# FPGA_Power.net
KiCad netlist of a schematic drawn in Altium Designer
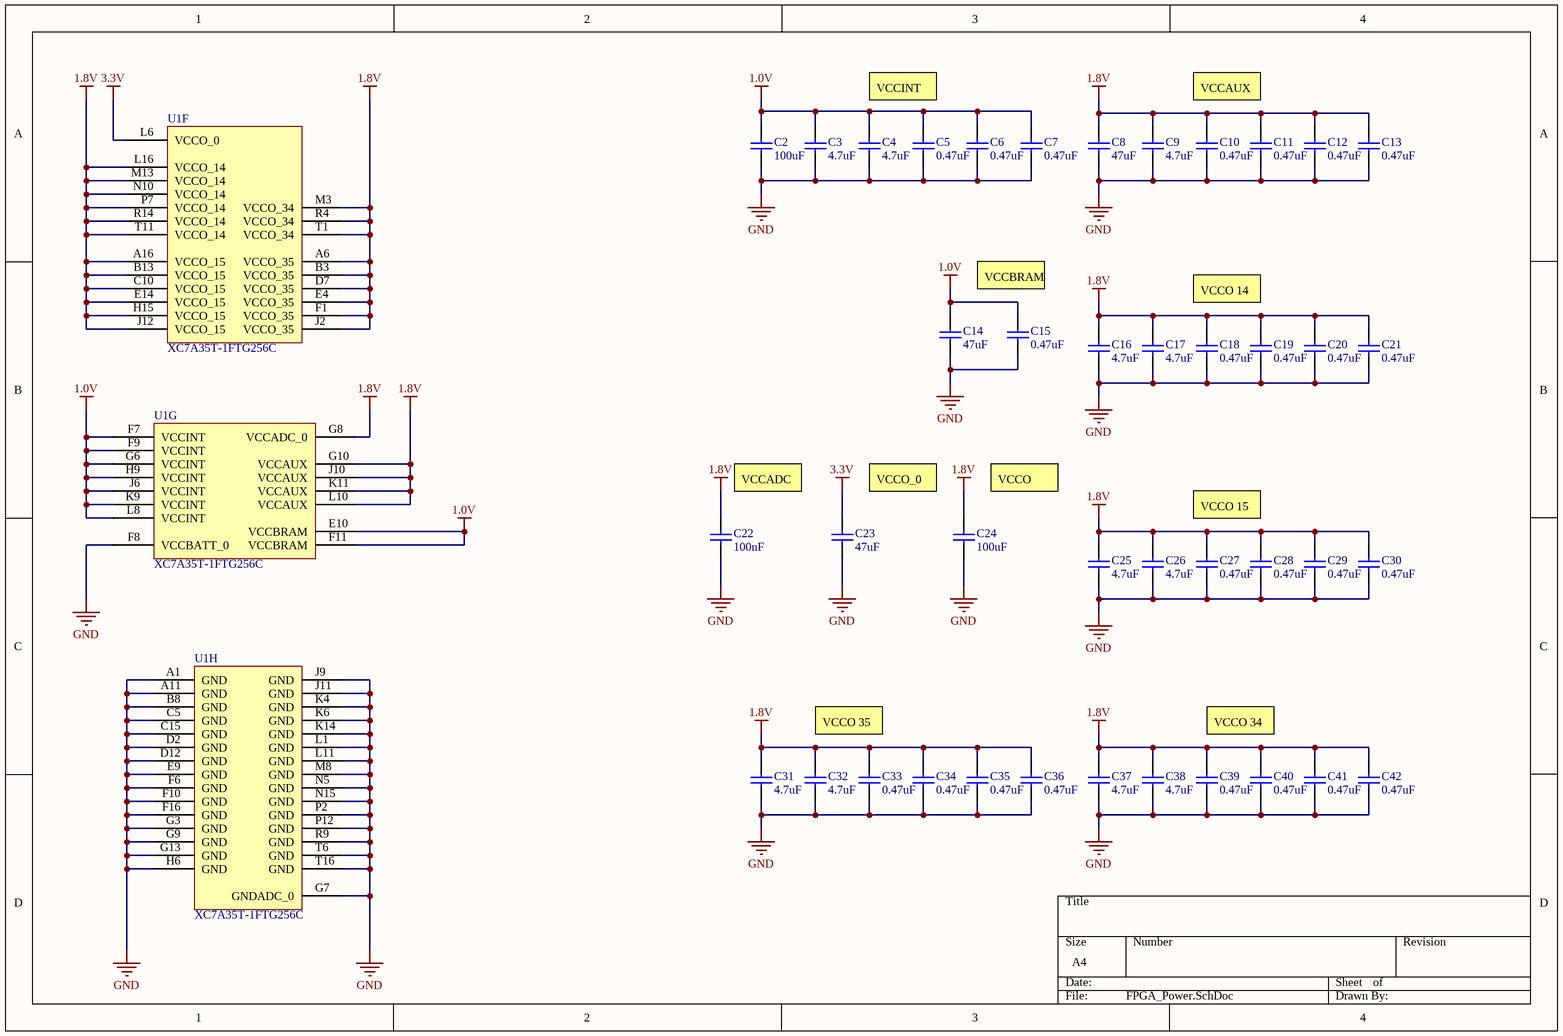
[diagram p0: FPGA_Power.SchDoc]

(export (version "E")
  (design (tool "Eeschema 10.0.6"))
  (components
    (comp (ref "C2")
      (value "100uF")
      (footprint "CAP1206")
      (fields (field (name "PART NUMBER") "GRM32ER60J107ME20L"))
      (libsource (lib "LimeMicroAltiumLib_schLib") (part "Cap_1206"))
    )
    (comp (ref "C3")
      (value "4.7uF")
      (footprint "CAP1206")
      (fields (field (name "PART NUMBER") "GRM32ER60J107ME20L"))
      (libsource (lib "LimeMicroAltiumLib_schLib") (part "Cap_1206"))
    )
    (comp (ref "C4")
      (value "4.7uF")
      (footprint "CAP1206")
      (fields (field (name "PART NUMBER") "GRM32ER60J107ME20L"))
      (libsource (lib "LimeMicroAltiumLib_schLib") (part "Cap_1206"))
    )
    (comp (ref "C5")
      (value "0.47uF")
      (footprint "CAP1206")
      (fields (field (name "PART NUMBER") "GRM32ER60J107ME20L"))
      (libsource (lib "LimeMicroAltiumLib_schLib") (part "Cap_1206"))
    )
    (comp (ref "C6")
      (value "0.47uF")
      (footprint "CAP1206")
      (fields (field (name "PART NUMBER") "GRM32ER60J107ME20L"))
      (libsource (lib "LimeMicroAltiumLib_schLib") (part "Cap_1206"))
    )
    (comp (ref "C7")
      (value "0.47uF")
      (footprint "CAP1206")
      (fields (field (name "PART NUMBER") "GRM32ER60J107ME20L"))
      (libsource (lib "LimeMicroAltiumLib_schLib") (part "Cap_1206"))
    )
    (comp (ref "C8")
      (value "47uF")
      (footprint "CAP1206")
      (fields (field (name "PART NUMBER") "GRM32ER60J107ME20L"))
      (libsource (lib "LimeMicroAltiumLib_schLib") (part "Cap_1206"))
    )
    (comp (ref "C9")
      (value "4.7uF")
      (footprint "CAP1206")
      (fields (field (name "PART NUMBER") "GRM32ER60J107ME20L"))
      (libsource (lib "LimeMicroAltiumLib_schLib") (part "Cap_1206"))
    )
    (comp (ref "C10")
      (value "0.47uF")
      (footprint "CAP1206")
      (fields (field (name "PART NUMBER") "GRM32ER60J107ME20L"))
      (libsource (lib "LimeMicroAltiumLib_schLib") (part "Cap_1206"))
    )
    (comp (ref "C11")
      (value "0.47uF")
      (footprint "CAP1206")
      (fields (field (name "PART NUMBER") "GRM32ER60J107ME20L"))
      (libsource (lib "LimeMicroAltiumLib_schLib") (part "Cap_1206"))
    )
    (comp (ref "C12")
      (value "0.47uF")
      (footprint "CAP1206")
      (fields (field (name "PART NUMBER") "GRM32ER60J107ME20L"))
      (libsource (lib "LimeMicroAltiumLib_schLib") (part "Cap_1206"))
    )
    (comp (ref "C13")
      (value "0.47uF")
      (footprint "CAP1206")
      (fields (field (name "PART NUMBER") "GRM32ER60J107ME20L"))
      (libsource (lib "LimeMicroAltiumLib_schLib") (part "Cap_1206"))
    )
    (comp (ref "C14")
      (value "47uF")
      (footprint "CAP1206")
      (fields (field (name "PART NUMBER") "GRM32ER60J107ME20L"))
      (libsource (lib "LimeMicroAltiumLib_schLib") (part "Cap_1206"))
    )
    (comp (ref "C15")
      (value "0.47uF")
      (footprint "CAP1206")
      (fields (field (name "PART NUMBER") "GRM32ER60J107ME20L"))
      (libsource (lib "LimeMicroAltiumLib_schLib") (part "Cap_1206"))
    )
    (comp (ref "C16")
      (value "4.7uF")
      (footprint "CAP1206")
      (fields (field (name "PART NUMBER") "GRM32ER60J107ME20L"))
      (libsource (lib "LimeMicroAltiumLib_schLib") (part "Cap_1206"))
    )
    (comp (ref "C17")
      (value "4.7uF")
      (footprint "CAP1206")
      (fields (field (name "PART NUMBER") "GRM32ER60J107ME20L"))
      (libsource (lib "LimeMicroAltiumLib_schLib") (part "Cap_1206"))
    )
    (comp (ref "C18")
      (value "0.47uF")
      (footprint "CAP1206")
      (fields (field (name "PART NUMBER") "GRM32ER60J107ME20L"))
      (libsource (lib "LimeMicroAltiumLib_schLib") (part "Cap_1206"))
    )
    (comp (ref "C19")
      (value "0.47uF")
      (footprint "CAP1206")
      (fields (field (name "PART NUMBER") "GRM32ER60J107ME20L"))
      (libsource (lib "LimeMicroAltiumLib_schLib") (part "Cap_1206"))
    )
    (comp (ref "C20")
      (value "0.47uF")
      (footprint "CAP1206")
      (fields (field (name "PART NUMBER") "GRM32ER60J107ME20L"))
      (libsource (lib "LimeMicroAltiumLib_schLib") (part "Cap_1206"))
    )
    (comp (ref "C21")
      (value "0.47uF")
      (footprint "CAP1206")
      (fields (field (name "PART NUMBER") "GRM32ER60J107ME20L"))
      (libsource (lib "LimeMicroAltiumLib_schLib") (part "Cap_1206"))
    )
    (comp (ref "C22")
      (value "100nF")
      (footprint "CAP1206")
      (fields (field (name "PART NUMBER") "GRM32ER60J107ME20L"))
      (libsource (lib "LimeMicroAltiumLib_schLib") (part "Cap_1206"))
    )
    (comp (ref "C23")
      (value "47uF")
      (footprint "CAP1206")
      (fields (field (name "PART NUMBER") "GRM32ER60J107ME20L"))
      (libsource (lib "LimeMicroAltiumLib_schLib") (part "Cap_1206"))
    )
    (comp (ref "C24")
      (value "100uF")
      (footprint "CAP1206")
      (fields (field (name "PART NUMBER") "GRM32ER60J107ME20L"))
      (libsource (lib "LimeMicroAltiumLib_schLib") (part "Cap_1206"))
    )
    (comp (ref "C25")
      (value "4.7uF")
      (footprint "CAP1206")
      (fields (field (name "PART NUMBER") "GRM32ER60J107ME20L"))
      (libsource (lib "LimeMicroAltiumLib_schLib") (part "Cap_1206"))
    )
    (comp (ref "C26")
      (value "4.7uF")
      (footprint "CAP1206")
      (fields (field (name "PART NUMBER") "GRM32ER60J107ME20L"))
      (libsource (lib "LimeMicroAltiumLib_schLib") (part "Cap_1206"))
    )
    (comp (ref "C27")
      (value "0.47uF")
      (footprint "CAP1206")
      (fields (field (name "PART NUMBER") "GRM32ER60J107ME20L"))
      (libsource (lib "LimeMicroAltiumLib_schLib") (part "Cap_1206"))
    )
    (comp (ref "C28")
      (value "0.47uF")
      (footprint "CAP1206")
      (fields (field (name "PART NUMBER") "GRM32ER60J107ME20L"))
      (libsource (lib "LimeMicroAltiumLib_schLib") (part "Cap_1206"))
    )
    (comp (ref "C29")
      (value "0.47uF")
      (footprint "CAP1206")
      (fields (field (name "PART NUMBER") "GRM32ER60J107ME20L"))
      (libsource (lib "LimeMicroAltiumLib_schLib") (part "Cap_1206"))
    )
    (comp (ref "C30")
      (value "0.47uF")
      (footprint "CAP1206")
      (fields (field (name "PART NUMBER") "GRM32ER60J107ME20L"))
      (libsource (lib "LimeMicroAltiumLib_schLib") (part "Cap_1206"))
    )
    (comp (ref "C31")
      (value "4.7uF")
      (footprint "CAP1206")
      (fields (field (name "PART NUMBER") "GRM32ER60J107ME20L"))
      (libsource (lib "LimeMicroAltiumLib_schLib") (part "Cap_1206"))
    )
    (comp (ref "C32")
      (value "4.7uF")
      (footprint "CAP1206")
      (fields (field (name "PART NUMBER") "GRM32ER60J107ME20L"))
      (libsource (lib "LimeMicroAltiumLib_schLib") (part "Cap_1206"))
    )
    (comp (ref "C33")
      (value "0.47uF")
      (footprint "CAP1206")
      (fields (field (name "PART NUMBER") "GRM32ER60J107ME20L"))
      (libsource (lib "LimeMicroAltiumLib_schLib") (part "Cap_1206"))
    )
    (comp (ref "C34")
      (value "0.47uF")
      (footprint "CAP1206")
      (fields (field (name "PART NUMBER") "GRM32ER60J107ME20L"))
      (libsource (lib "LimeMicroAltiumLib_schLib") (part "Cap_1206"))
    )
    (comp (ref "C35")
      (value "0.47uF")
      (footprint "CAP1206")
      (fields (field (name "PART NUMBER") "GRM32ER60J107ME20L"))
      (libsource (lib "LimeMicroAltiumLib_schLib") (part "Cap_1206"))
    )
    (comp (ref "C36")
      (value "0.47uF")
      (footprint "CAP1206")
      (fields (field (name "PART NUMBER") "GRM32ER60J107ME20L"))
      (libsource (lib "LimeMicroAltiumLib_schLib") (part "Cap_1206"))
    )
    (comp (ref "C37")
      (value "4.7uF")
      (footprint "CAP1206")
      (fields (field (name "PART NUMBER") "GRM32ER60J107ME20L"))
      (libsource (lib "LimeMicroAltiumLib_schLib") (part "Cap_1206"))
    )
    (comp (ref "C38")
      (value "4.7uF")
      (footprint "CAP1206")
      (fields (field (name "PART NUMBER") "GRM32ER60J107ME20L"))
      (libsource (lib "LimeMicroAltiumLib_schLib") (part "Cap_1206"))
    )
    (comp (ref "C39")
      (value "0.47uF")
      (footprint "CAP1206")
      (fields (field (name "PART NUMBER") "GRM32ER60J107ME20L"))
      (libsource (lib "LimeMicroAltiumLib_schLib") (part "Cap_1206"))
    )
    (comp (ref "C40")
      (value "0.47uF")
      (footprint "CAP1206")
      (fields (field (name "PART NUMBER") "GRM32ER60J107ME20L"))
      (libsource (lib "LimeMicroAltiumLib_schLib") (part "Cap_1206"))
    )
    (comp (ref "C41")
      (value "0.47uF")
      (footprint "CAP1206")
      (fields (field (name "PART NUMBER") "GRM32ER60J107ME20L"))
      (libsource (lib "LimeMicroAltiumLib_schLib") (part "Cap_1206"))
    )
    (comp (ref "C42")
      (value "0.47uF")
      (footprint "CAP1206")
      (fields (field (name "PART NUMBER") "GRM32ER60J107ME20L"))
      (libsource (lib "LimeMicroAltiumLib_schLib") (part "Cap_1206"))
    )
    (comp (ref "U1")
      (value "XC7A35T-1FTG256C")
      (footprint "FTG256")
      (description "Artix-7 FPGA, 170 User I/Os, 0 GTP, 256-Ball BGA, Speed Grade 1, Commercial Grade, Pb-Free")
      (fields (field (name "MANUFACTURER") "Xilinx"))
      (libsource (lib "Xilinx Artix-7") (part "XC7A35T-1FTG256C"))
    )
  )
  (nets
    (net (code "1") (name "1.0V") (class "Default")
      (node (ref "C14") (pin "1") (pinfunction "1_1") (pintype "passive"))
      (node (ref "C15") (pin "1") (pinfunction "1_1") (pintype "passive"))
      (node (ref "C2") (pin "1") (pinfunction "1_1") (pintype "passive"))
      (node (ref "C3") (pin "1") (pinfunction "1_1") (pintype "passive"))
      (node (ref "C4") (pin "1") (pinfunction "1_1") (pintype "passive"))
      (node (ref "C5") (pin "1") (pinfunction "1_1") (pintype "passive"))
      (node (ref "C6") (pin "1") (pinfunction "1_1") (pintype "passive"))
      (node (ref "C7") (pin "1") (pinfunction "1_1") (pintype "passive"))
      (node (ref "U1") (pin "E10") (pinfunction "VCCBRAM_E10") (pintype "power_in"))
      (node (ref "U1") (pin "F11") (pinfunction "VCCBRAM_F11") (pintype "power_in"))
      (node (ref "U1") (pin "F7") (pinfunction "VCCINT_F7") (pintype "power_in"))
      (node (ref "U1") (pin "F9") (pinfunction "VCCINT_F9") (pintype "power_in"))
      (node (ref "U1") (pin "G6") (pinfunction "VCCINT_G6") (pintype "power_in"))
      (node (ref "U1") (pin "H9") (pinfunction "VCCINT_H9") (pintype "power_in"))
      (node (ref "U1") (pin "J6") (pinfunction "VCCINT_J6") (pintype "power_in"))
      (node (ref "U1") (pin "K9") (pinfunction "VCCINT_K9") (pintype "power_in"))
      (node (ref "U1") (pin "L8") (pinfunction "VCCINT_L8") (pintype "power_in"))
    )
    (net (code "2") (name "1.8V") (class "Default")
      (node (ref "C10") (pin "1") (pinfunction "1_1") (pintype "passive"))
      (node (ref "C11") (pin "1") (pinfunction "1_1") (pintype "passive"))
      (node (ref "C12") (pin "1") (pinfunction "1_1") (pintype "passive"))
      (node (ref "C13") (pin "1") (pinfunction "1_1") (pintype "passive"))
      (node (ref "C16") (pin "1") (pinfunction "1_1") (pintype "passive"))
      (node (ref "C17") (pin "1") (pinfunction "1_1") (pintype "passive"))
      (node (ref "C18") (pin "1") (pinfunction "1_1") (pintype "passive"))
      (node (ref "C19") (pin "1") (pinfunction "1_1") (pintype "passive"))
      (node (ref "C20") (pin "1") (pinfunction "1_1") (pintype "passive"))
      (node (ref "C21") (pin "1") (pinfunction "1_1") (pintype "passive"))
      (node (ref "C22") (pin "1") (pinfunction "1_1") (pintype "passive"))
      (node (ref "C24") (pin "1") (pinfunction "1_1") (pintype "passive"))
      (node (ref "C25") (pin "1") (pinfunction "1_1") (pintype "passive"))
      (node (ref "C26") (pin "1") (pinfunction "1_1") (pintype "passive"))
      (node (ref "C27") (pin "1") (pinfunction "1_1") (pintype "passive"))
      (node (ref "C28") (pin "1") (pinfunction "1_1") (pintype "passive"))
      (node (ref "C29") (pin "1") (pinfunction "1_1") (pintype "passive"))
      (node (ref "C30") (pin "1") (pinfunction "1_1") (pintype "passive"))
      (node (ref "C31") (pin "1") (pinfunction "1_1") (pintype "passive"))
      (node (ref "C32") (pin "1") (pinfunction "1_1") (pintype "passive"))
      (node (ref "C33") (pin "1") (pinfunction "1_1") (pintype "passive"))
      (node (ref "C34") (pin "1") (pinfunction "1_1") (pintype "passive"))
      (node (ref "C35") (pin "1") (pinfunction "1_1") (pintype "passive"))
      (node (ref "C36") (pin "1") (pinfunction "1_1") (pintype "passive"))
      (node (ref "C37") (pin "1") (pinfunction "1_1") (pintype "passive"))
      (node (ref "C38") (pin "1") (pinfunction "1_1") (pintype "passive"))
      (node (ref "C39") (pin "1") (pinfunction "1_1") (pintype "passive"))
      (node (ref "C40") (pin "1") (pinfunction "1_1") (pintype "passive"))
      (node (ref "C41") (pin "1") (pinfunction "1_1") (pintype "passive"))
      (node (ref "C42") (pin "1") (pinfunction "1_1") (pintype "passive"))
      (node (ref "C8") (pin "1") (pinfunction "1_1") (pintype "passive"))
      (node (ref "C9") (pin "1") (pinfunction "1_1") (pintype "passive"))
      (node (ref "U1") (pin "A16") (pinfunction "VCCO_15_A16") (pintype "power_in"))
      (node (ref "U1") (pin "A6") (pinfunction "VCCO_35_A6") (pintype "power_in"))
      (node (ref "U1") (pin "B13") (pinfunction "VCCO_15_B13") (pintype "power_in"))
      (node (ref "U1") (pin "B3") (pinfunction "VCCO_35_B3") (pintype "power_in"))
      (node (ref "U1") (pin "C10") (pinfunction "VCCO_15_C10") (pintype "power_in"))
      (node (ref "U1") (pin "D7") (pinfunction "VCCO_35_D7") (pintype "power_in"))
      (node (ref "U1") (pin "E14") (pinfunction "VCCO_15_E14") (pintype "power_in"))
      (node (ref "U1") (pin "E4") (pinfunction "VCCO_35_E4") (pintype "power_in"))
      (node (ref "U1") (pin "F1") (pinfunction "VCCO_35_F1") (pintype "power_in"))
      (node (ref "U1") (pin "G10") (pinfunction "VCCAUX_G10") (pintype "power_in"))
      (node (ref "U1") (pin "G8") (pinfunction "VCCADC_0_G8") (pintype "power_in"))
      (node (ref "U1") (pin "H15") (pinfunction "VCCO_15_H15") (pintype "power_in"))
      (node (ref "U1") (pin "J10") (pinfunction "VCCAUX_J10") (pintype "power_in"))
      (node (ref "U1") (pin "J12") (pinfunction "VCCO_15_J12") (pintype "power_in"))
      (node (ref "U1") (pin "J2") (pinfunction "VCCO_35_J2") (pintype "power_in"))
      (node (ref "U1") (pin "K11") (pinfunction "VCCAUX_K11") (pintype "power_in"))
      (node (ref "U1") (pin "L10") (pinfunction "VCCAUX_L10") (pintype "power_in"))
      (node (ref "U1") (pin "L16") (pinfunction "VCCO_14_L16") (pintype "power_in"))
      (node (ref "U1") (pin "M13") (pinfunction "VCCO_14_M13") (pintype "power_in"))
      (node (ref "U1") (pin "M3") (pinfunction "VCCO_34_M3") (pintype "power_in"))
      (node (ref "U1") (pin "N10") (pinfunction "VCCO_14_N10") (pintype "power_in"))
      (node (ref "U1") (pin "P7") (pinfunction "VCCO_14_P7") (pintype "power_in"))
      (node (ref "U1") (pin "R14") (pinfunction "VCCO_14_R14") (pintype "power_in"))
      (node (ref "U1") (pin "R4") (pinfunction "VCCO_34_R4") (pintype "power_in"))
      (node (ref "U1") (pin "T1") (pinfunction "VCCO_34_T1") (pintype "power_in"))
      (node (ref "U1") (pin "T11") (pinfunction "VCCO_14_T11") (pintype "power_in"))
    )
    (net (code "3") (name "3.3V") (class "Default")
      (node (ref "C23") (pin "1") (pinfunction "1_1") (pintype "passive"))
      (node (ref "U1") (pin "L6") (pinfunction "VCCO_0_L6") (pintype "power_in"))
    )
    (net (code "4") (name "GND") (class "Default")
      (node (ref "C10") (pin "2") (pinfunction "2_2") (pintype "passive"))
      (node (ref "C11") (pin "2") (pinfunction "2_2") (pintype "passive"))
      (node (ref "C12") (pin "2") (pinfunction "2_2") (pintype "passive"))
      (node (ref "C13") (pin "2") (pinfunction "2_2") (pintype "passive"))
      (node (ref "C14") (pin "2") (pinfunction "2_2") (pintype "passive"))
      (node (ref "C15") (pin "2") (pinfunction "2_2") (pintype "passive"))
      (node (ref "C16") (pin "2") (pinfunction "2_2") (pintype "passive"))
      (node (ref "C17") (pin "2") (pinfunction "2_2") (pintype "passive"))
      (node (ref "C18") (pin "2") (pinfunction "2_2") (pintype "passive"))
      (node (ref "C19") (pin "2") (pinfunction "2_2") (pintype "passive"))
      (node (ref "C2") (pin "2") (pinfunction "2_2") (pintype "passive"))
      (node (ref "C20") (pin "2") (pinfunction "2_2") (pintype "passive"))
      (node (ref "C21") (pin "2") (pinfunction "2_2") (pintype "passive"))
      (node (ref "C22") (pin "2") (pinfunction "2_2") (pintype "passive"))
      (node (ref "C23") (pin "2") (pinfunction "2_2") (pintype "passive"))
      (node (ref "C24") (pin "2") (pinfunction "2_2") (pintype "passive"))
      (node (ref "C25") (pin "2") (pinfunction "2_2") (pintype "passive"))
      (node (ref "C26") (pin "2") (pinfunction "2_2") (pintype "passive"))
      (node (ref "C27") (pin "2") (pinfunction "2_2") (pintype "passive"))
      (node (ref "C28") (pin "2") (pinfunction "2_2") (pintype "passive"))
      (node (ref "C29") (pin "2") (pinfunction "2_2") (pintype "passive"))
      (node (ref "C3") (pin "2") (pinfunction "2_2") (pintype "passive"))
      (node (ref "C30") (pin "2") (pinfunction "2_2") (pintype "passive"))
      (node (ref "C31") (pin "2") (pinfunction "2_2") (pintype "passive"))
      (node (ref "C32") (pin "2") (pinfunction "2_2") (pintype "passive"))
      (node (ref "C33") (pin "2") (pinfunction "2_2") (pintype "passive"))
      (node (ref "C34") (pin "2") (pinfunction "2_2") (pintype "passive"))
      (node (ref "C35") (pin "2") (pinfunction "2_2") (pintype "passive"))
      (node (ref "C36") (pin "2") (pinfunction "2_2") (pintype "passive"))
      (node (ref "C37") (pin "2") (pinfunction "2_2") (pintype "passive"))
      (node (ref "C38") (pin "2") (pinfunction "2_2") (pintype "passive"))
      (node (ref "C39") (pin "2") (pinfunction "2_2") (pintype "passive"))
      (node (ref "C4") (pin "2") (pinfunction "2_2") (pintype "passive"))
      (node (ref "C40") (pin "2") (pinfunction "2_2") (pintype "passive"))
      (node (ref "C41") (pin "2") (pinfunction "2_2") (pintype "passive"))
      (node (ref "C42") (pin "2") (pinfunction "2_2") (pintype "passive"))
      (node (ref "C5") (pin "2") (pinfunction "2_2") (pintype "passive"))
      (node (ref "C6") (pin "2") (pinfunction "2_2") (pintype "passive"))
      (node (ref "C7") (pin "2") (pinfunction "2_2") (pintype "passive"))
      (node (ref "C8") (pin "2") (pinfunction "2_2") (pintype "passive"))
      (node (ref "C9") (pin "2") (pinfunction "2_2") (pintype "passive"))
      (node (ref "U1") (pin "A1") (pinfunction "GND_A1") (pintype "power_in"))
      (node (ref "U1") (pin "A11") (pinfunction "GND_A11") (pintype "power_in"))
      (node (ref "U1") (pin "B8") (pinfunction "GND_B8") (pintype "power_in"))
      (node (ref "U1") (pin "C15") (pinfunction "GND_C15") (pintype "power_in"))
      (node (ref "U1") (pin "C5") (pinfunction "GND_C5") (pintype "power_in"))
      (node (ref "U1") (pin "D12") (pinfunction "GND_D12") (pintype "power_in"))
      (node (ref "U1") (pin "D2") (pinfunction "GND_D2") (pintype "power_in"))
      (node (ref "U1") (pin "E9") (pinfunction "GND_E9") (pintype "power_in"))
      (node (ref "U1") (pin "F10") (pinfunction "GND_F10") (pintype "power_in"))
      (node (ref "U1") (pin "F16") (pinfunction "GND_F16") (pintype "power_in"))
      (node (ref "U1") (pin "F6") (pinfunction "GND_F6") (pintype "power_in"))
      (node (ref "U1") (pin "F8") (pinfunction "VCCBATT_0_F8") (pintype "power_in"))
      (node (ref "U1") (pin "G13") (pinfunction "GND_G13") (pintype "power_in"))
      (node (ref "U1") (pin "G3") (pinfunction "GND_G3") (pintype "power_in"))
      (node (ref "U1") (pin "G7") (pinfunction "GNDADC_0_G7") (pintype "power_in"))
      (node (ref "U1") (pin "G9") (pinfunction "GND_G9") (pintype "power_in"))
      (node (ref "U1") (pin "H6") (pinfunction "GND_H6") (pintype "power_in"))
      (node (ref "U1") (pin "J11") (pinfunction "GND_J11") (pintype "power_in"))
      (node (ref "U1") (pin "J9") (pinfunction "GND_J9") (pintype "power_in"))
      (node (ref "U1") (pin "K14") (pinfunction "GND_K14") (pintype "power_in"))
      (node (ref "U1") (pin "K4") (pinfunction "GND_K4") (pintype "power_in"))
      (node (ref "U1") (pin "K6") (pinfunction "GND_K6") (pintype "power_in"))
      (node (ref "U1") (pin "L1") (pinfunction "GND_L1") (pintype "power_in"))
      (node (ref "U1") (pin "L11") (pinfunction "GND_L11") (pintype "power_in"))
      (node (ref "U1") (pin "M8") (pinfunction "GND_M8") (pintype "power_in"))
      (node (ref "U1") (pin "N15") (pinfunction "GND_N15") (pintype "power_in"))
      (node (ref "U1") (pin "N5") (pinfunction "GND_N5") (pintype "power_in"))
      (node (ref "U1") (pin "P12") (pinfunction "GND_P12") (pintype "power_in"))
      (node (ref "U1") (pin "P2") (pinfunction "GND_P2") (pintype "power_in"))
      (node (ref "U1") (pin "R9") (pinfunction "GND_R9") (pintype "power_in"))
      (node (ref "U1") (pin "T16") (pinfunction "GND_T16") (pintype "power_in"))
      (node (ref "U1") (pin "T6") (pinfunction "GND_T6") (pintype "power_in"))
    )
  )
)
